# rpi_board.net
KiCad netlist of a schematic drawn in EAGLE
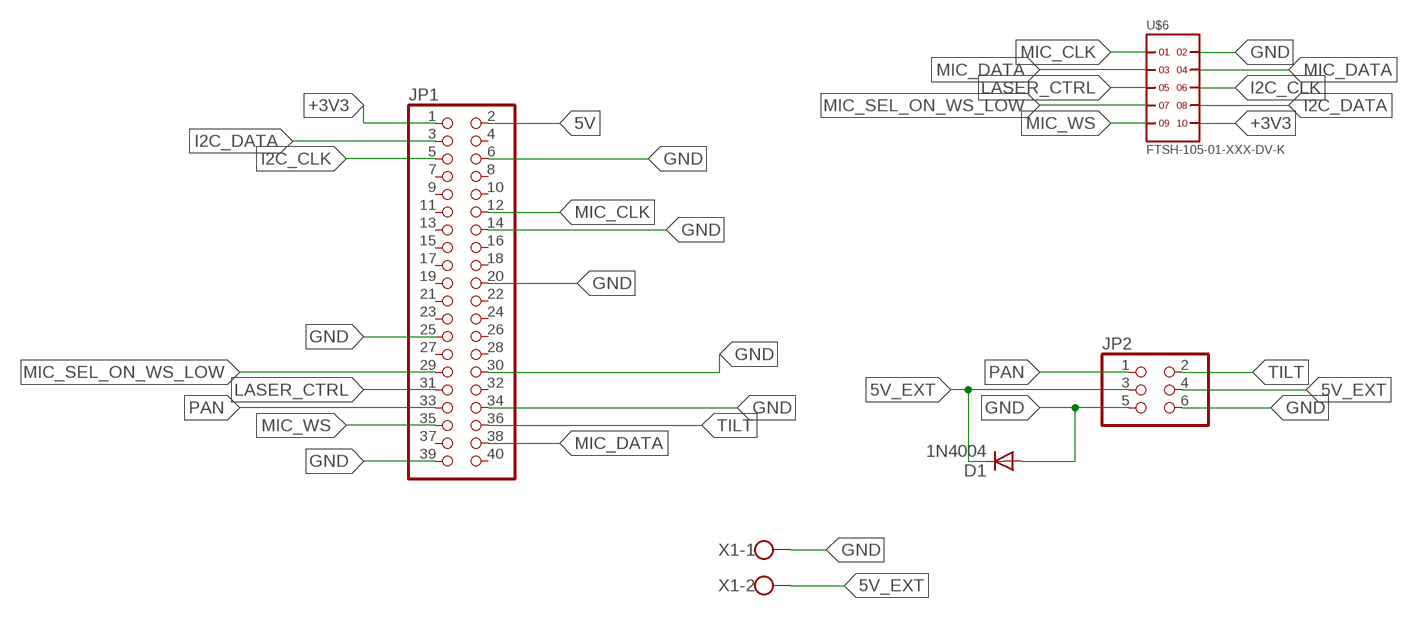
[diagram p0: schematic, sheet 1]

(export (version "E")
  (design (tool "Eeschema 10.0.6"))
  (components
    (comp (ref "D1")
      (value "1N4004")
      (footprint "eagle-import:DO41-10")
      (libsource (lib "eagle-import") (part "1N4004"))
    )
    (comp (ref "JP1")
      (value "PINHD-2X20")
      (footprint "eagle-import:2X20")
      (libsource (lib "eagle-import") (part "PINHD-2X20"))
    )
    (comp (ref "JP2")
      (value "PINHD-2X3")
      (footprint "eagle-import:2X03")
      (libsource (lib "eagle-import") (part "PINHD-2X3"))
    )
    (comp (ref "U$6")
      (value "FTSH-105-01-XXX-DV-K")
      (footprint "eagle-import:FTSH-105-01-XXX-DV-K")
      (libsource (lib "eagle-import") (part "FTSH-105-01-XXX-DV-K"))
    )
    (comp (ref "X1")
      (value "W237-102")
      (footprint "eagle-import:W237-102")
      (fields (field (name "MPN") "237-102"))
      (libsource (lib "eagle-import") (part "W237-102"))
    )
  )
  (nets
    (net (code "1") (name "+3V3") (class "Default")
      (node (ref "JP1") (pin "1") (pinfunction "1_1") (pintype "passive"))
      (node (ref "U$6") (pin "10") (pinfunction "10_10") (pintype "bidirectional"))
    )
    (net (code "2") (name "5V") (class "Default")
      (node (ref "JP1") (pin "2") (pinfunction "2_2") (pintype "passive"))
    )
    (net (code "3") (name "5V_EXT") (class "Default")
      (node (ref "D1") (pin "C") (pinfunction "C_C") (pintype "passive"))
      (node (ref "JP2") (pin "3") (pinfunction "3_3") (pintype "passive"))
      (node (ref "JP2") (pin "4") (pinfunction "4_4") (pintype "passive"))
      (node (ref "X1") (pin "2") (pinfunction "KL_2") (pintype "passive"))
    )
    (net (code "4") (name "GND") (class "Default")
      (node (ref "D1") (pin "A") (pinfunction "A_A") (pintype "passive"))
      (node (ref "JP1") (pin "14") (pinfunction "14_14") (pintype "passive"))
      (node (ref "JP1") (pin "20") (pinfunction "20_20") (pintype "passive"))
      (node (ref "JP1") (pin "25") (pinfunction "25_25") (pintype "passive"))
      (node (ref "JP1") (pin "30") (pinfunction "30_30") (pintype "passive"))
      (node (ref "JP1") (pin "34") (pinfunction "34_34") (pintype "passive"))
      (node (ref "JP1") (pin "39") (pinfunction "39_39") (pintype "passive"))
      (node (ref "JP1") (pin "6") (pinfunction "6_6") (pintype "passive"))
      (node (ref "JP2") (pin "5") (pinfunction "5_5") (pintype "passive"))
      (node (ref "JP2") (pin "6") (pinfunction "6_6") (pintype "passive"))
      (node (ref "U$6") (pin "2") (pinfunction "2_2") (pintype "bidirectional"))
      (node (ref "X1") (pin "1") (pinfunction "KL_1") (pintype "passive"))
    )
    (net (code "5") (name "I2C_CLK") (class "Default")
      (node (ref "JP1") (pin "5") (pinfunction "5_5") (pintype "passive"))
      (node (ref "U$6") (pin "6") (pinfunction "6_6") (pintype "bidirectional"))
    )
    (net (code "6") (name "I2C_DATA") (class "Default")
      (node (ref "JP1") (pin "3") (pinfunction "3_3") (pintype "passive"))
      (node (ref "U$6") (pin "8") (pinfunction "8_8") (pintype "bidirectional"))
    )
    (net (code "7") (name "LASER_CTRL") (class "Default")
      (node (ref "JP1") (pin "31") (pinfunction "31_31") (pintype "passive"))
      (node (ref "U$6") (pin "5") (pinfunction "5_5") (pintype "bidirectional"))
    )
    (net (code "8") (name "MIC_CLK") (class "Default")
      (node (ref "JP1") (pin "12") (pinfunction "12_12") (pintype "passive"))
      (node (ref "U$6") (pin "1") (pinfunction "1_1") (pintype "bidirectional"))
    )
    (net (code "9") (name "MIC_DATA") (class "Default")
      (node (ref "JP1") (pin "38") (pinfunction "38_38") (pintype "passive"))
      (node (ref "U$6") (pin "3") (pinfunction "3_3") (pintype "bidirectional"))
      (node (ref "U$6") (pin "4") (pinfunction "4_4") (pintype "bidirectional"))
    )
    (net (code "10") (name "MIC_SEL_ON_WS_LOW") (class "Default")
      (node (ref "JP1") (pin "29") (pinfunction "29_29") (pintype "passive"))
      (node (ref "U$6") (pin "7") (pinfunction "7_7") (pintype "bidirectional"))
    )
    (net (code "11") (name "MIC_WS") (class "Default")
      (node (ref "JP1") (pin "35") (pinfunction "35_35") (pintype "passive"))
      (node (ref "U$6") (pin "9") (pinfunction "9_9") (pintype "bidirectional"))
    )
    (net (code "12") (name "PAN") (class "Default")
      (node (ref "JP1") (pin "33") (pinfunction "33_33") (pintype "passive"))
      (node (ref "JP2") (pin "1") (pinfunction "1_1") (pintype "passive"))
    )
    (net (code "13") (name "TILT") (class "Default")
      (node (ref "JP1") (pin "36") (pinfunction "36_36") (pintype "passive"))
      (node (ref "JP2") (pin "2") (pinfunction "2_2") (pintype "passive"))
    )
    (net (code "14") (name "unconnected-(JP1-Pad4)") (class "Default")
      (node (ref "JP1") (pin "4") (pinfunction "4_4") (pintype "passive"))
    )
    (net (code "15") (name "unconnected-(JP1-Pad7)") (class "Default")
      (node (ref "JP1") (pin "7") (pinfunction "7_7") (pintype "passive"))
    )
    (net (code "16") (name "unconnected-(JP1-Pad8)") (class "Default")
      (node (ref "JP1") (pin "8") (pinfunction "8_8") (pintype "passive"))
    )
    (net (code "17") (name "unconnected-(JP1-Pad9)") (class "Default")
      (node (ref "JP1") (pin "9") (pinfunction "9_9") (pintype "passive"))
    )
    (net (code "18") (name "unconnected-(JP1-Pad10)") (class "Default")
      (node (ref "JP1") (pin "10") (pinfunction "10_10") (pintype "passive"))
    )
    (net (code "19") (name "unconnected-(JP1-Pad11)") (class "Default")
      (node (ref "JP1") (pin "11") (pinfunction "11_11") (pintype "passive"))
    )
    (net (code "20") (name "unconnected-(JP1-Pad13)") (class "Default")
      (node (ref "JP1") (pin "13") (pinfunction "13_13") (pintype "passive"))
    )
    (net (code "21") (name "unconnected-(JP1-Pad15)") (class "Default")
      (node (ref "JP1") (pin "15") (pinfunction "15_15") (pintype "passive"))
    )
    (net (code "22") (name "unconnected-(JP1-Pad16)") (class "Default")
      (node (ref "JP1") (pin "16") (pinfunction "16_16") (pintype "passive"))
    )
    (net (code "23") (name "unconnected-(JP1-Pad17)") (class "Default")
      (node (ref "JP1") (pin "17") (pinfunction "17_17") (pintype "passive"))
    )
    (net (code "24") (name "unconnected-(JP1-Pad18)") (class "Default")
      (node (ref "JP1") (pin "18") (pinfunction "18_18") (pintype "passive"))
    )
    (net (code "25") (name "unconnected-(JP1-Pad19)") (class "Default")
      (node (ref "JP1") (pin "19") (pinfunction "19_19") (pintype "passive"))
    )
    (net (code "26") (name "unconnected-(JP1-Pad21)") (class "Default")
      (node (ref "JP1") (pin "21") (pinfunction "21_21") (pintype "passive"))
    )
    (net (code "27") (name "unconnected-(JP1-Pad22)") (class "Default")
      (node (ref "JP1") (pin "22") (pinfunction "22_22") (pintype "passive"))
    )
    (net (code "28") (name "unconnected-(JP1-Pad23)") (class "Default")
      (node (ref "JP1") (pin "23") (pinfunction "23_23") (pintype "passive"))
    )
    (net (code "29") (name "unconnected-(JP1-Pad24)") (class "Default")
      (node (ref "JP1") (pin "24") (pinfunction "24_24") (pintype "passive"))
    )
    (net (code "30") (name "unconnected-(JP1-Pad26)") (class "Default")
      (node (ref "JP1") (pin "26") (pinfunction "26_26") (pintype "passive"))
    )
    (net (code "31") (name "unconnected-(JP1-Pad27)") (class "Default")
      (node (ref "JP1") (pin "27") (pinfunction "27_27") (pintype "passive"))
    )
    (net (code "32") (name "unconnected-(JP1-Pad28)") (class "Default")
      (node (ref "JP1") (pin "28") (pinfunction "28_28") (pintype "passive"))
    )
    (net (code "33") (name "unconnected-(JP1-Pad32)") (class "Default")
      (node (ref "JP1") (pin "32") (pinfunction "32_32") (pintype "passive"))
    )
    (net (code "34") (name "unconnected-(JP1-Pad37)") (class "Default")
      (node (ref "JP1") (pin "37") (pinfunction "37_37") (pintype "passive"))
    )
    (net (code "35") (name "unconnected-(JP1-Pad40)") (class "Default")
      (node (ref "JP1") (pin "40") (pinfunction "40_40") (pintype "passive"))
    )
  )
)
